# ATmega324PB_Xplained_Pro_triple_input_po.net
KiCad netlist of a schematic drawn in Altium Designer
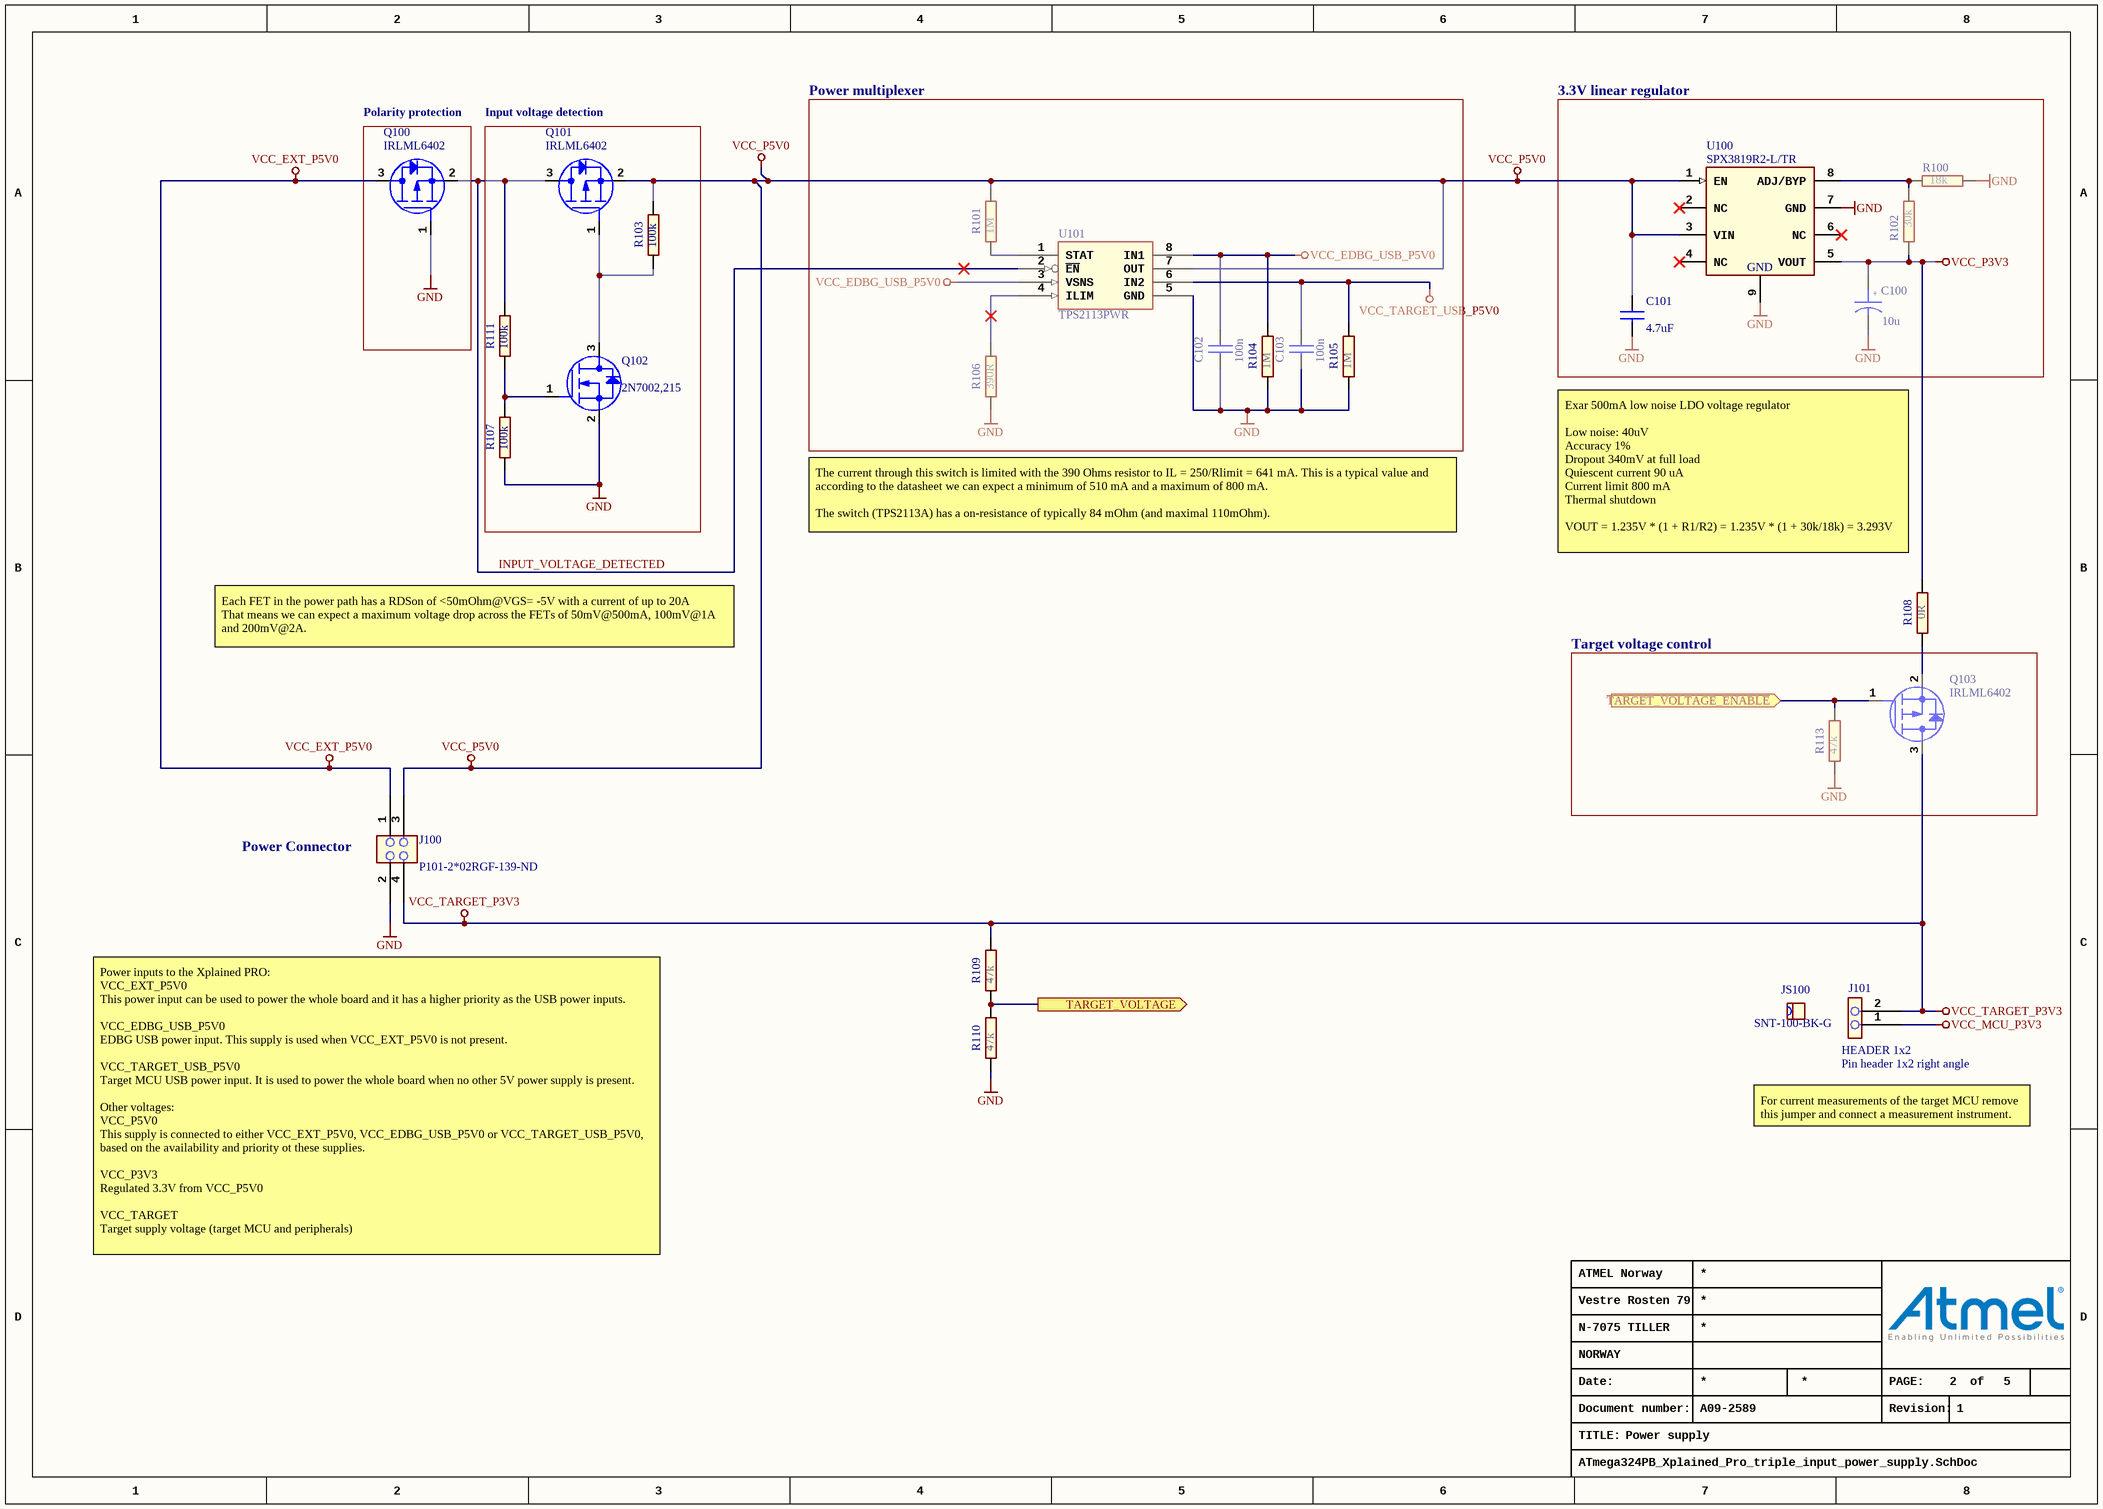
[diagram p0: ATmega324PB_Xplained_Pro_triple_input_power_supply.SchDoc]

(export (version "E")
  (design (tool "Eeschema 10.0.6"))
  (components
    (comp (ref "C100")
      (value "10u")
      (footprint "AP1-00036")
      (description "SMD tantalum capacitor, ESR = 1.7, 3216-18 (EIA) 1206,")
      (fields
        (field (name "TOLERANCE") "+-10%")
        (field (name "MANUFACTURER") "vishay")
        (field (name "VERIFIED BY") "Ketil Skjerve")
      )
      (libsource (lib "AltiumDbLib") (part "CAP-POL"))
    )
    (comp (ref "C101")
      (value "4.7uF")
      (footprint "AP1-00039")
      (description "Ceramic capacitor, SMD 0603, X5R, 10V, 10% (de31036)")
      (fields
        (field (name "TOLERANCE") "10%")
        (field (name "MANUFACTURER") "tdk")
        (field (name "VERIFIED BY") "Lars Helge Mo")
      )
      (libsource (lib "AltiumDbLib") (part "CAP-NONPOL"))
    )
    (comp (ref "C102")
      (value "100n")
      (footprint "AP1-00053")
      (description "Ceramic capacitor, SMD 0402, X7R, 16V, +/-10%")
      (fields
        (field (name "TOLERANCE") "16V, +/-10%")
        (field (name "MANUFACTURER") "Kemet")
        (field (name "VERIFIED BY") "Lars Helge Mo")
      )
      (libsource (lib "AltiumDbLib") (part "CAP-NONPOL"))
    )
    (comp (ref "C103")
      (value "100n")
      (footprint "AP1-00053")
      (description "Ceramic capacitor, SMD 0402, X7R, 16V, +/-10%")
      (fields
        (field (name "TOLERANCE") "16V, +/-10%")
        (field (name "MANUFACTURER") "Kemet")
        (field (name "VERIFIED BY") "Lars Helge Mo")
      )
      (libsource (lib "AltiumDbLib") (part "CAP-NONPOL"))
    )
    (comp (ref "J100")
      (value "P101-2*02RGF-139-ND")
      (footprint "AP8-00628")
      (description "Pin header, 2x2, Right Angle, 2.54mm, THT, Pin In Paste")
      (fields (field (name "Comment") "HEADER 2x2") (field (name "VERIFIED BY") "Lars Helge Mo"))
      (libsource (lib "AltiumDbLib") (part "HEADER 2x2"))
    )
    (comp (ref "J101")
      (value "HEADER 1x2")
      (footprint "AP8-00367")
      (description "1x2 pin header, right angle, 2.54 mm pitch, through-hole")
      (fields
        (field (name "ALTIUM_VALUE") "Pin header 1x2 right angle")
        (field (name "MANUFACTURER") "Pro-data International Corp")
        (field (name "MPN") "2213R-2G")
        (field (name "VERIFIED BY") "Lars Helge")
      )
      (libsource (lib "AltiumDbLib") (part "HEADER 1x2"))
    )
    (comp (ref "JS100")
      (value "SNT-100-BK-G")
      (footprint "AP8-00525")
      (description "Jumper cap for 2.54mm pinheader")
      (fields
        (field (name "MANUFACTURER") "SAMTEC")
        (field (name "Comment") "To be used by request from ESCATEC")
        (field (name "VERIFIED BY") "Lars Helge Mo")
      )
      (libsource (lib "AltiumDbLib") (part "JUMPER_CAP"))
    )
    (comp (ref "Q100")
      (value "IRLML6402")
      (footprint "AP5-00002")
      (description "P-ch. MOSFET. -30V, -3.7A continuous,RDS(ON)=0.05Ohm@VGS=-4,5V, RDS(ON)=0.08Ohm@VGS=-2.5V")
      (fields (field (name "MANUFACTURER") "International Rectifier") (field (name "MPN") "IRLML6402PBF"))
      (libsource (lib "AltiumDbLib") (part "MOSFET_P_GSD"))
    )
    (comp (ref "Q101")
      (value "IRLML6402")
      (footprint "AP5-00002")
      (description "P-ch. MOSFET. -30V, -3.7A continuous,RDS(ON)=0.05Ohm@VGS=-4,5V, RDS(ON)=0.08Ohm@VGS=-2.5V")
      (fields (field (name "MANUFACTURER") "International Rectifier") (field (name "MPN") "IRLML6402PBF"))
      (libsource (lib "AltiumDbLib") (part "MOSFET_P_GSD"))
    )
    (comp (ref "Q102")
      (value "2N7002,215")
      (footprint "AP5-00002")
      (description "N-Channel MOSFET. 60V, 0.300A continuous, 1.2A Peak. RDS(ON) = 3.8Ohm@VGS=4.5V, VGS(th)<2.5V")
      (fields (field (name "MANUFACTURER") "NXP") (field (name "Comment") "MOSFET_N_GSD"))
      (libsource (lib "AltiumDbLib") (part "MOSFET_N_GSD"))
    )
    (comp (ref "Q103")
      (value "IRLML6402")
      (footprint "AP5-00002")
      (description "P-ch. MOSFET. -30V, -3.7A continuous,RDS(ON)=0.05Ohm@VGS=-4,5V, RDS(ON)=0.08Ohm@VGS=-2.5V")
      (fields (field (name "MANUFACTURER") "International Rectifier") (field (name "MPN") "IRLML6402PBF"))
      (libsource (lib "AltiumDbLib") (part "MOSFET_P_GSD"))
    )
    (comp (ref "R100")
      (value "18k")
      (footprint "AP2-00000")
      (description "Thick film resistor, SMD 0402, 1/16W, 1%")
      (fields
        (field (name "TOLERANCE") "1 %")
        (field (name "Comment") "R2")
        (field (name "VERIFIED BY") "Lars Helge Mo")
      )
      (libsource (lib "AltiumDbLib") (part "R2"))
    )
    (comp (ref "R101")
      (value "1M")
      (footprint "AP2-00011")
      (description "Thick film resistor, SMD 0402, 1/16W, 1%")
      (fields
        (field (name "TOLERANCE") "1 %")
        (field (name "Comment") "R2")
        (field (name "VERIFIED BY") "Lars Helge Mo")
      )
      (libsource (lib "") (part "R2_1"))
    )
    (comp (ref "R102")
      (value "30k")
      (footprint "AP2-00000")
      (description "Thick film resistor, SMD 0402, 1/16W, 1%")
      (fields
        (field (name "TOLERANCE") "1 %")
        (field (name "Comment") "R2")
        (field (name "VERIFIED BY") "Lars Helge Mo")
      )
      (libsource (lib "") (part "R2_1"))
    )
    (comp (ref "R103")
      (value "100k")
      (footprint "AP2-00000")
      (description "Thick film resistor, SMD 0402, 1/16W, 1%")
      (fields
        (field (name "TOLERANCE") "1 %")
        (field (name "Comment") "R2")
        (field (name "VERIFIED BY") "Lars Helge Mo")
      )
      (libsource (lib "") (part "R2_1"))
    )
    (comp (ref "R104")
      (value "1M")
      (footprint "AP2-00011")
      (description "Thick film resistor, SMD 0402, 1/16W, 1%")
      (fields
        (field (name "TOLERANCE") "1 %")
        (field (name "Comment") "R2")
        (field (name "VERIFIED BY") "Lars Helge Mo")
      )
      (libsource (lib "") (part "R2_1"))
    )
    (comp (ref "R105")
      (value "1M")
      (footprint "AP2-00011")
      (description "Thick film resistor, SMD 0402, 1/16W, 1%")
      (fields
        (field (name "TOLERANCE") "1 %")
        (field (name "Comment") "R2")
        (field (name "VERIFIED BY") "Lars Helge Mo")
      )
      (libsource (lib "") (part "R2_1"))
    )
    (comp (ref "R106")
      (value "390R")
      (footprint "AP2-00011")
      (description "Thick film resistor, SMD 0402, 1/16W, 1%")
      (fields
        (field (name "TOLERANCE") "1 %")
        (field (name "Comment") "R2")
        (field (name "VERIFIED BY") "Lars Helge Mo")
      )
      (libsource (lib "") (part "R2_1"))
    )
    (comp (ref "R107")
      (value "100k")
      (footprint "AP2-00000")
      (description "Thick film resistor, SMD 0402, 1/16W, 1%")
      (fields
        (field (name "TOLERANCE") "1 %")
        (field (name "Comment") "R2")
        (field (name "VERIFIED BY") "Lars Helge Mo")
      )
      (libsource (lib "") (part "R2_1"))
    )
    (comp (ref "R108")
      (value "0R")
      (footprint "AP2-00000")
      (description "Thick film resistor, SMD 0402, 1/16W, 1%")
      (fields
        (field (name "TOLERANCE") "1 %")
        (field (name "Comment") "R2")
        (field (name "VERIFIED BY") "Lars Helge Mo")
      )
      (libsource (lib "") (part "R2_3"))
    )
    (comp (ref "R109")
      (value "47k")
      (footprint "AP2-00000")
      (description "Thick film resistor, SMD 0402, 1/16W, 1%")
      (fields
        (field (name "TOLERANCE") "1 %")
        (field (name "Comment") "R2")
        (field (name "VERIFIED BY") "Lars Helge Mo")
      )
      (libsource (lib "") (part "R2_2"))
    )
    (comp (ref "R110")
      (value "47k")
      (footprint "AP2-00000")
      (description "Thick film resistor, SMD 0402, 1/16W, 1%")
      (fields
        (field (name "TOLERANCE") "1 %")
        (field (name "Comment") "R2")
        (field (name "VERIFIED BY") "Lars Helge Mo")
      )
      (libsource (lib "") (part "R2_2"))
    )
    (comp (ref "R111")
      (value "100k")
      (footprint "AP2-00000")
      (description "Thick film resistor, SMD 0402, 1/16W, 1%")
      (fields
        (field (name "TOLERANCE") "1 %")
        (field (name "Comment") "R2")
        (field (name "VERIFIED BY") "Lars Helge Mo")
      )
      (libsource (lib "") (part "R2_1"))
    )
    (comp (ref "R113")
      (value "47k")
      (footprint "AP2-00011")
      (description "Thick film resistor, SMD 0402, 1/16W, 1%")
      (fields
        (field (name "TOLERANCE") "1 %")
        (field (name "Comment") "R2")
        (field (name "VERIFIED BY") "Lars Helge Mo")
      )
      (libsource (lib "") (part "R2_2"))
    )
    (comp (ref "U100")
      (value "SPX3819R2-L/TR")
      (footprint "AP6-00338")
      (description "500mA LDO, ADJ, low noise, 8-DFN package")
      (fields (field (name "TOLERANCE") "±1%") (field (name "MANUFACTURER") "Exar"))
      (libsource (lib "AltiumDbLib") (part "SPX3819R2-L"))
    )
    (comp (ref "U101")
      (value "TPS2113PWR")
      (footprint "AP6-00054")
      (description "Autoswitching 2:1 Power Mux")
      (fields
        (field (name "MANUFACTURER") "Texas Instruments")
        (field (name "Comment") "TPS2112")
        (field (name "VERIFIED BY") "Sveinung Helgeland")
      )
      (libsource (lib "AltiumDbLib") (part "TPS2112"))
    )
  )
  (nets
    (net (code "1") (name "/INPUT_VOLTAGE_DETECTED") (class "Default")
      (node (ref "Q100") (pin "2") (pinfunction "S_2") (pintype "passive"))
      (node (ref "Q101") (pin "3") (pinfunction "D_3") (pintype "passive"))
      (node (ref "R111") (pin "2") (pinfunction "2_2") (pintype "passive"))
      (node (ref "U101") (pin "2") (pinfunction "~{EN}_2") (pintype "input"))
    )
    (net (code "2") (name "/TARGET_VOLTAGE") (class "Default")
      (node (ref "R109") (pin "1") (pinfunction "1_1") (pintype "passive"))
      (node (ref "R110") (pin "2") (pinfunction "2_2") (pintype "passive"))
    )
    (net (code "3") (name "/~{TARGET_VOLTAGE_ENABLE}") (class "Default")
      (node (ref "Q103") (pin "1") (pinfunction "G_1") (pintype "passive"))
      (node (ref "R113") (pin "2") (pinfunction "2_2") (pintype "passive"))
    )
    (net (code "4") (name "GND") (class "Default")
      (node (ref "C100") (pin "2") (pinfunction "2_2") (pintype "passive"))
      (node (ref "C101") (pin "2") (pinfunction "2_2") (pintype "passive"))
      (node (ref "C102") (pin "2") (pinfunction "2_2") (pintype "passive"))
      (node (ref "C103") (pin "2") (pinfunction "2_2") (pintype "passive"))
      (node (ref "J100") (pin "2") (pinfunction "2_2") (pintype "passive"))
      (node (ref "Q100") (pin "1") (pinfunction "G_1") (pintype "passive"))
      (node (ref "Q102") (pin "2") (pinfunction "S_2") (pintype "passive"))
      (node (ref "R100") (pin "2") (pinfunction "2_2") (pintype "passive"))
      (node (ref "R104") (pin "1") (pinfunction "1_1") (pintype "passive"))
      (node (ref "R105") (pin "1") (pinfunction "1_1") (pintype "passive"))
      (node (ref "R106") (pin "1") (pinfunction "1_1") (pintype "passive"))
      (node (ref "R107") (pin "1") (pinfunction "1_1") (pintype "passive"))
      (node (ref "R110") (pin "1") (pinfunction "1_1") (pintype "passive"))
      (node (ref "R113") (pin "1") (pinfunction "1_1") (pintype "passive"))
      (node (ref "U100") (pin "7") (pinfunction "GND_7") (pintype "power_in"))
      (node (ref "U100") (pin "9") (pinfunction "GND_9") (pintype "power_in"))
      (node (ref "U101") (pin "5") (pinfunction "GND_5") (pintype "power_in"))
    )
    (net (code "5") (name "Net-(Q101-G)") (class "Default")
      (node (ref "Q101") (pin "1") (pinfunction "G_1") (pintype "passive"))
      (node (ref "Q102") (pin "3") (pinfunction "D_3") (pintype "passive"))
      (node (ref "R103") (pin "1") (pinfunction "1_1") (pintype "passive"))
    )
    (net (code "6") (name "Net-(Q102-G)") (class "Default")
      (node (ref "Q102") (pin "1") (pinfunction "G_1") (pintype "passive"))
      (node (ref "R107") (pin "2") (pinfunction "2_2") (pintype "passive"))
      (node (ref "R111") (pin "1") (pinfunction "1_1") (pintype "passive"))
    )
    (net (code "7") (name "Net-(Q103-S)") (class "Default")
      (node (ref "Q103") (pin "2") (pinfunction "S_2") (pintype "passive"))
      (node (ref "R108") (pin "2") (pinfunction "2_2") (pintype "passive"))
    )
    (net (code "8") (name "Net-(U100-ADJ{slash}BYP)") (class "Default")
      (node (ref "R100") (pin "1") (pinfunction "1_1") (pintype "passive"))
      (node (ref "R102") (pin "2") (pinfunction "2_2") (pintype "passive"))
      (node (ref "U100") (pin "8") (pinfunction "ADJ/BYP_8") (pintype "passive"))
    )
    (net (code "9") (name "Net-(U101-ILIM)") (class "Default")
      (node (ref "R106") (pin "2") (pinfunction "2_2") (pintype "passive"))
      (node (ref "U101") (pin "4") (pinfunction "ILIM_4") (pintype "input"))
    )
    (net (code "10") (name "Net-(U101-STAT)") (class "Default")
      (node (ref "R101") (pin "1") (pinfunction "1_1") (pintype "passive"))
      (node (ref "U101") (pin "1") (pinfunction "STAT_1") (pintype "open_collector"))
    )
    (net (code "11") (name "VCC_EDBG_USB_P5V0") (class "Default")
      (node (ref "C102") (pin "1") (pinfunction "1_1") (pintype "passive"))
      (node (ref "R104") (pin "2") (pinfunction "2_2") (pintype "passive"))
      (node (ref "U101") (pin "3") (pinfunction "VSNS_3") (pintype "input"))
      (node (ref "U101") (pin "8") (pinfunction "IN1_8") (pintype "power_in"))
    )
    (net (code "12") (name "VCC_EXT_P5V0") (class "Default")
      (node (ref "J100") (pin "1") (pinfunction "1_1") (pintype "passive"))
      (node (ref "Q100") (pin "3") (pinfunction "D_3") (pintype "passive"))
    )
    (net (code "13") (name "VCC_MCU_P3V3") (class "Default")
      (node (ref "J101") (pin "1") (pinfunction "1_1") (pintype "passive"))
    )
    (net (code "14") (name "VCC_P3V3") (class "Default")
      (node (ref "C100") (pin "1") (pinfunction "1_1") (pintype "passive"))
      (node (ref "R102") (pin "1") (pinfunction "1_1") (pintype "passive"))
      (node (ref "R108") (pin "1") (pinfunction "1_1") (pintype "passive"))
      (node (ref "U100") (pin "5") (pinfunction "VOUT_5") (pintype "power_in"))
    )
    (net (code "15") (name "VCC_P5V0") (class "Default")
      (node (ref "C101") (pin "1") (pinfunction "1_1") (pintype "passive"))
      (node (ref "J100") (pin "3") (pinfunction "3_3") (pintype "passive"))
      (node (ref "Q101") (pin "2") (pinfunction "S_2") (pintype "passive"))
      (node (ref "R101") (pin "2") (pinfunction "2_2") (pintype "passive"))
      (node (ref "R103") (pin "2") (pinfunction "2_2") (pintype "passive"))
      (node (ref "U100") (pin "1") (pinfunction "EN_1") (pintype "input"))
      (node (ref "U100") (pin "3") (pinfunction "VIN_3") (pintype "power_in"))
      (node (ref "U101") (pin "7") (pinfunction "OUT_7") (pintype "power_in"))
    )
    (net (code "16") (name "VCC_TARGET_P3V3") (class "Default")
      (node (ref "J100") (pin "4") (pinfunction "4_4") (pintype "passive"))
      (node (ref "J101") (pin "2") (pinfunction "2_2") (pintype "passive"))
      (node (ref "Q103") (pin "3") (pinfunction "D_3") (pintype "passive"))
      (node (ref "R109") (pin "2") (pinfunction "2_2") (pintype "passive"))
    )
    (net (code "17") (name "VCC_TARGET_USB_P5V0") (class "Default")
      (node (ref "C103") (pin "1") (pinfunction "1_1") (pintype "passive"))
      (node (ref "R105") (pin "2") (pinfunction "2_2") (pintype "passive"))
      (node (ref "U101") (pin "6") (pinfunction "IN2_6") (pintype "power_in"))
    )
    (net (code "18") (name "unconnected-(U100-NC-Pad2)") (class "Default")
      (node (ref "U100") (pin "2") (pinfunction "NC_2") (pintype "passive+no_connect"))
    )
    (net (code "19") (name "unconnected-(U100-NC-Pad4)") (class "Default")
      (node (ref "U100") (pin "4") (pinfunction "NC_4") (pintype "passive+no_connect"))
    )
    (net (code "20") (name "unconnected-(U100-NC-Pad6)") (class "Default")
      (node (ref "U100") (pin "6") (pinfunction "NC_6") (pintype "passive+no_connect"))
    )
  )
)
